# SR-Daughter.net
KiCad netlist of a schematic drawn in EAGLE
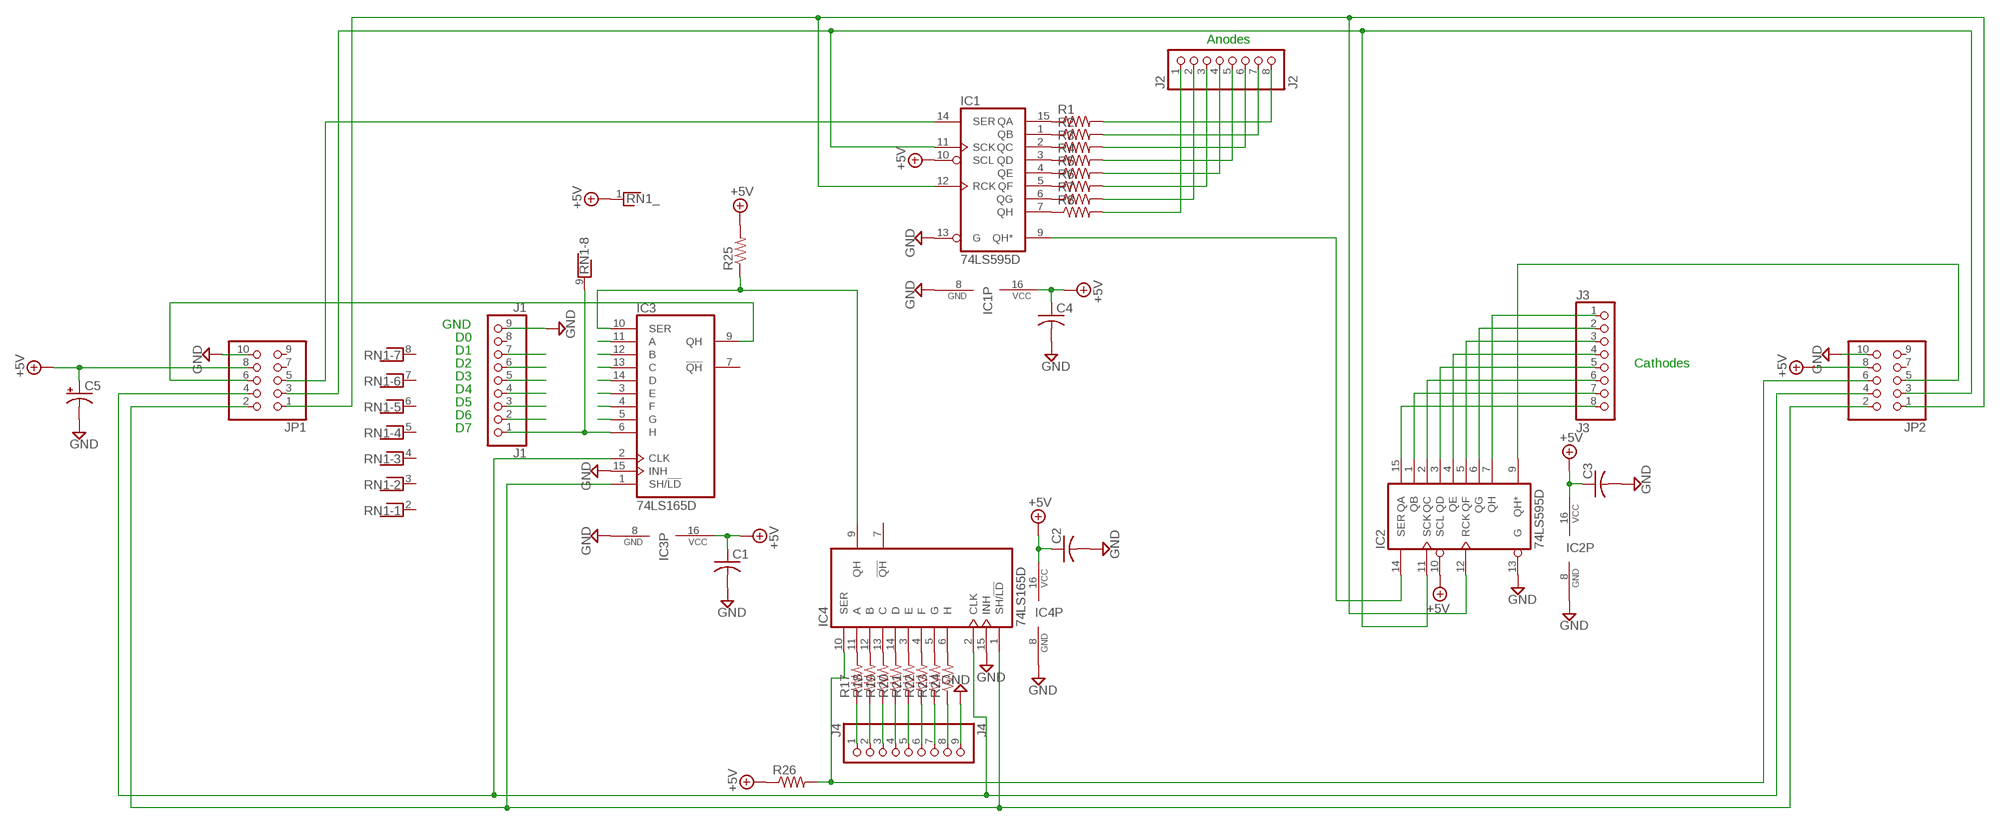
[diagram p0: schematic, sheet 1]

(export (version "E")
  (design (tool "Eeschema 10.0.6"))
  (components
    (comp (ref "C1")
      (value "C-USC0603")
      (footprint "eagle-import:C0603")
      (libsource (lib "eagle-import") (part "C-USC0603"))
    )
    (comp (ref "C2")
      (value "C-USC0603")
      (footprint "eagle-import:C0603")
      (libsource (lib "eagle-import") (part "C-USC0603"))
    )
    (comp (ref "C3")
      (value "C-USC0603")
      (footprint "eagle-import:C0603")
      (libsource (lib "eagle-import") (part "C-USC0603"))
    )
    (comp (ref "C4")
      (value "C-USC0603")
      (footprint "eagle-import:C0603")
      (libsource (lib "eagle-import") (part "C-USC0603"))
    )
    (comp (ref "C5")
      (value "CPOL-USE2-5")
      (footprint "eagle-import:E2-5")
      (libsource (lib "eagle-import") (part "CPOL-USE2-5"))
    )
    (comp (ref "IC1")
      (value "74LS595D")
      (footprint "eagle-import:SO16")
      (libsource (lib "eagle-import") (part "74595DLS"))
    )
    (comp (ref "IC2")
      (value "74LS595D")
      (footprint "eagle-import:SO16")
      (libsource (lib "eagle-import") (part "74595DLS"))
    )
    (comp (ref "IC3")
      (value "74LS165D")
      (footprint "eagle-import:SO16")
      (libsource (lib "eagle-import") (part "74165DLS"))
    )
    (comp (ref "IC4")
      (value "74LS165D")
      (footprint "eagle-import:SO16")
      (libsource (lib "eagle-import") (part "74165DLS"))
    )
    (comp (ref "J1")
      (value "J1")
      (footprint "eagle-import:1X09")
      (libsource (lib "eagle-import") (part "PINHD-1X9"))
    )
    (comp (ref "J2")
      (value "J2")
      (footprint "eagle-import:1X08")
      (libsource (lib "eagle-import") (part "PINHD-1X8"))
    )
    (comp (ref "J3")
      (value "J3")
      (footprint "eagle-import:1X08")
      (libsource (lib "eagle-import") (part "PINHD-1X8"))
    )
    (comp (ref "J4")
      (value "J4")
      (footprint "eagle-import:1X09")
      (libsource (lib "eagle-import") (part "PINHD-1X9"))
    )
    (comp (ref "JP1")
      (value "PINHD-2X5")
      (footprint "eagle-import:2X05")
      (libsource (lib "eagle-import") (part "PINHD-2X5"))
    )
    (comp (ref "JP2")
      (value "PINHD-2X5")
      (footprint "eagle-import:2X05")
      (libsource (lib "eagle-import") (part "PINHD-2X5"))
    )
    (comp (ref "R1")
      (value "R-US_M0805")
      (footprint "eagle-import:M0805")
      (libsource (lib "eagle-import") (part "R-US_M0805"))
    )
    (comp (ref "R2")
      (value "R-US_M0805")
      (footprint "eagle-import:M0805")
      (libsource (lib "eagle-import") (part "R-US_M0805"))
    )
    (comp (ref "R3")
      (value "R-US_M0805")
      (footprint "eagle-import:M0805")
      (libsource (lib "eagle-import") (part "R-US_M0805"))
    )
    (comp (ref "R4")
      (value "R-US_M0805")
      (footprint "eagle-import:M0805")
      (libsource (lib "eagle-import") (part "R-US_M0805"))
    )
    (comp (ref "R5")
      (value "R-US_M0805")
      (footprint "eagle-import:M0805")
      (libsource (lib "eagle-import") (part "R-US_M0805"))
    )
    (comp (ref "R6")
      (value "R-US_M0805")
      (footprint "eagle-import:M0805")
      (libsource (lib "eagle-import") (part "R-US_M0805"))
    )
    (comp (ref "R7")
      (value "R-US_M0805")
      (footprint "eagle-import:M0805")
      (libsource (lib "eagle-import") (part "R-US_M0805"))
    )
    (comp (ref "R8")
      (value "R-US_M0805")
      (footprint "eagle-import:M0805")
      (libsource (lib "eagle-import") (part "R-US_M0805"))
    )
    (comp (ref "R17")
      (value "R-US_M0805")
      (footprint "eagle-import:M0805")
      (libsource (lib "eagle-import") (part "R-US_M0805"))
    )
    (comp (ref "R18")
      (value "R-US_M0805")
      (footprint "eagle-import:M0805")
      (libsource (lib "eagle-import") (part "R-US_M0805"))
    )
    (comp (ref "R19")
      (value "R-US_M0805")
      (footprint "eagle-import:M0805")
      (libsource (lib "eagle-import") (part "R-US_M0805"))
    )
    (comp (ref "R20")
      (value "R-US_M0805")
      (footprint "eagle-import:M0805")
      (libsource (lib "eagle-import") (part "R-US_M0805"))
    )
    (comp (ref "R21")
      (value "R-US_M0805")
      (footprint "eagle-import:M0805")
      (libsource (lib "eagle-import") (part "R-US_M0805"))
    )
    (comp (ref "R22")
      (value "R-US_M0805")
      (footprint "eagle-import:M0805")
      (libsource (lib "eagle-import") (part "R-US_M0805"))
    )
    (comp (ref "R23")
      (value "R-US_M0805")
      (footprint "eagle-import:M0805")
      (libsource (lib "eagle-import") (part "R-US_M0805"))
    )
    (comp (ref "R24")
      (value "R-US_M0805")
      (footprint "eagle-import:M0805")
      (libsource (lib "eagle-import") (part "R-US_M0805"))
    )
    (comp (ref "R25")
      (value "R-US_M0805")
      (footprint "eagle-import:M0805")
      (libsource (lib "eagle-import") (part "R-US_M0805"))
    )
    (comp (ref "R26")
      (value "R-US_M0805")
      (footprint "eagle-import:M0805")
      (libsource (lib "eagle-import") (part "R-US_M0805"))
    )
    (comp (ref "RN1")
      (value "RNX8")
      (footprint "eagle-import:RN-9")
      (libsource (lib "eagle-import") (part "RNX8"))
    )
  )
  (nets
    (net (code "1") (name "+5V") (class "Default")
      (node (ref "C1") (pin "1") (pinfunction "1_1") (pintype "passive"))
      (node (ref "C2") (pin "1") (pinfunction "1_1") (pintype "passive"))
      (node (ref "C3") (pin "1") (pinfunction "1_1") (pintype "passive"))
      (node (ref "C4") (pin "1") (pinfunction "1_1") (pintype "passive"))
      (node (ref "C5") (pin "+") (pinfunction "+_+") (pintype "passive"))
      (node (ref "IC1") (pin "10") (pinfunction "SCL_10") (pintype "input"))
      (node (ref "IC1") (pin "16") (pinfunction "VCC_16") (pintype "power_in"))
      (node (ref "IC2") (pin "10") (pinfunction "SCL_10") (pintype "input"))
      (node (ref "IC2") (pin "16") (pinfunction "VCC_16") (pintype "power_in"))
      (node (ref "IC3") (pin "16") (pinfunction "VCC_16") (pintype "power_in"))
      (node (ref "IC4") (pin "16") (pinfunction "VCC_16") (pintype "power_in"))
      (node (ref "JP1") (pin "8") (pinfunction "8_8") (pintype "passive"))
      (node (ref "JP2") (pin "8") (pinfunction "8_8") (pintype "passive"))
      (node (ref "R25") (pin "2") (pinfunction "2_2") (pintype "passive"))
      (node (ref "R26") (pin "1") (pinfunction "1_1") (pintype "passive"))
      (node (ref "RN1") (pin "1") (pinfunction "1_1") (pintype "passive"))
    )
    (net (code "2") (name "GND") (class "Default")
      (node (ref "C1") (pin "2") (pinfunction "2_2") (pintype "passive"))
      (node (ref "C2") (pin "2") (pinfunction "2_2") (pintype "passive"))
      (node (ref "C3") (pin "2") (pinfunction "2_2") (pintype "passive"))
      (node (ref "C4") (pin "2") (pinfunction "2_2") (pintype "passive"))
      (node (ref "C5") (pin "-") (pinfunction "-_-") (pintype "passive"))
      (node (ref "IC1") (pin "13") (pinfunction "G_13") (pintype "input"))
      (node (ref "IC1") (pin "8") (pinfunction "GND_8") (pintype "power_in"))
      (node (ref "IC2") (pin "13") (pinfunction "G_13") (pintype "input"))
      (node (ref "IC2") (pin "8") (pinfunction "GND_8") (pintype "power_in"))
      (node (ref "IC3") (pin "15") (pinfunction "INH_15") (pintype "input"))
      (node (ref "IC3") (pin "8") (pinfunction "GND_8") (pintype "power_in"))
      (node (ref "IC4") (pin "15") (pinfunction "INH_15") (pintype "input"))
      (node (ref "IC4") (pin "8") (pinfunction "GND_8") (pintype "power_in"))
      (node (ref "J1") (pin "9") (pinfunction "9_9") (pintype "passive"))
      (node (ref "J4") (pin "9") (pinfunction "9_9") (pintype "passive"))
      (node (ref "JP1") (pin "10") (pinfunction "10_10") (pintype "passive"))
      (node (ref "JP2") (pin "10") (pinfunction "10_10") (pintype "passive"))
    )
    (net (code "3") (name "Net-(IC1A-QA)") (class "Default")
      (node (ref "IC1") (pin "15") (pinfunction "QA_15") (pintype "tri_state"))
      (node (ref "R1") (pin "1") (pinfunction "1_1") (pintype "passive"))
    )
    (net (code "4") (name "Net-(IC1A-QB)") (class "Default")
      (node (ref "IC1") (pin "1") (pinfunction "QB_1") (pintype "tri_state"))
      (node (ref "R2") (pin "1") (pinfunction "1_1") (pintype "passive"))
    )
    (net (code "5") (name "Net-(IC1A-QC)") (class "Default")
      (node (ref "IC1") (pin "2") (pinfunction "QC_2") (pintype "tri_state"))
      (node (ref "R3") (pin "1") (pinfunction "1_1") (pintype "passive"))
    )
    (net (code "6") (name "Net-(IC1A-QD)") (class "Default")
      (node (ref "IC1") (pin "3") (pinfunction "QD_3") (pintype "tri_state"))
      (node (ref "R4") (pin "1") (pinfunction "1_1") (pintype "passive"))
    )
    (net (code "7") (name "Net-(IC1A-QE)") (class "Default")
      (node (ref "IC1") (pin "4") (pinfunction "QE_4") (pintype "tri_state"))
      (node (ref "R5") (pin "1") (pinfunction "1_1") (pintype "passive"))
    )
    (net (code "8") (name "Net-(IC1A-QF)") (class "Default")
      (node (ref "IC1") (pin "5") (pinfunction "QF_5") (pintype "tri_state"))
      (node (ref "R6") (pin "1") (pinfunction "1_1") (pintype "passive"))
    )
    (net (code "9") (name "Net-(IC1A-QG)") (class "Default")
      (node (ref "IC1") (pin "6") (pinfunction "QG_6") (pintype "tri_state"))
      (node (ref "R7") (pin "1") (pinfunction "1_1") (pintype "passive"))
    )
    (net (code "10") (name "Net-(IC1A-QH)") (class "Default")
      (node (ref "IC1") (pin "7") (pinfunction "QH_7") (pintype "tri_state"))
      (node (ref "R8") (pin "1") (pinfunction "1_1") (pintype "passive"))
    )
    (net (code "11") (name "Net-(IC1A-QH*)") (class "Default")
      (node (ref "IC1") (pin "9") (pinfunction "QH*_9") (pintype "tri_state"))
      (node (ref "IC2") (pin "14") (pinfunction "SER_14") (pintype "input"))
    )
    (net (code "12") (name "Net-(IC1A-RCK)") (class "Default")
      (node (ref "IC1") (pin "12") (pinfunction "RCK_12") (pintype "input"))
      (node (ref "IC2") (pin "12") (pinfunction "RCK_12") (pintype "input"))
      (node (ref "JP1") (pin "1") (pinfunction "1_1") (pintype "passive"))
      (node (ref "JP2") (pin "1") (pinfunction "1_1") (pintype "passive"))
    )
    (net (code "13") (name "Net-(IC1A-SCK)") (class "Default")
      (node (ref "IC1") (pin "11") (pinfunction "SCK_11") (pintype "input"))
      (node (ref "IC2") (pin "11") (pinfunction "SCK_11") (pintype "input"))
      (node (ref "JP1") (pin "3") (pinfunction "3_3") (pintype "passive"))
      (node (ref "JP2") (pin "3") (pinfunction "3_3") (pintype "passive"))
    )
    (net (code "14") (name "Net-(IC1A-SER)") (class "Default")
      (node (ref "IC1") (pin "14") (pinfunction "SER_14") (pintype "input"))
      (node (ref "JP1") (pin "5") (pinfunction "5_5") (pintype "passive"))
    )
    (net (code "15") (name "Net-(IC2A-QA)") (class "Default")
      (node (ref "IC2") (pin "15") (pinfunction "QA_15") (pintype "tri_state"))
      (node (ref "J3") (pin "8") (pinfunction "8_8") (pintype "passive"))
    )
    (net (code "16") (name "Net-(IC2A-QB)") (class "Default")
      (node (ref "IC2") (pin "1") (pinfunction "QB_1") (pintype "tri_state"))
      (node (ref "J3") (pin "7") (pinfunction "7_7") (pintype "passive"))
    )
    (net (code "17") (name "Net-(IC2A-QC)") (class "Default")
      (node (ref "IC2") (pin "2") (pinfunction "QC_2") (pintype "tri_state"))
      (node (ref "J3") (pin "6") (pinfunction "6_6") (pintype "passive"))
    )
    (net (code "18") (name "Net-(IC2A-QD)") (class "Default")
      (node (ref "IC2") (pin "3") (pinfunction "QD_3") (pintype "tri_state"))
      (node (ref "J3") (pin "5") (pinfunction "5_5") (pintype "passive"))
    )
    (net (code "19") (name "Net-(IC2A-QE)") (class "Default")
      (node (ref "IC2") (pin "4") (pinfunction "QE_4") (pintype "tri_state"))
      (node (ref "J3") (pin "4") (pinfunction "4_4") (pintype "passive"))
    )
    (net (code "20") (name "Net-(IC2A-QF)") (class "Default")
      (node (ref "IC2") (pin "5") (pinfunction "QF_5") (pintype "tri_state"))
      (node (ref "J3") (pin "3") (pinfunction "3_3") (pintype "passive"))
    )
    (net (code "21") (name "Net-(IC2A-QG)") (class "Default")
      (node (ref "IC2") (pin "6") (pinfunction "QG_6") (pintype "tri_state"))
      (node (ref "J3") (pin "2") (pinfunction "2_2") (pintype "passive"))
    )
    (net (code "22") (name "Net-(IC2A-QH)") (class "Default")
      (node (ref "IC2") (pin "7") (pinfunction "QH_7") (pintype "tri_state"))
      (node (ref "J3") (pin "1") (pinfunction "1_1") (pintype "passive"))
    )
    (net (code "23") (name "Net-(IC2A-QH*)") (class "Default")
      (node (ref "IC2") (pin "9") (pinfunction "QH*_9") (pintype "tri_state"))
      (node (ref "JP2") (pin "5") (pinfunction "5_5") (pintype "passive"))
    )
    (net (code "24") (name "Net-(IC3A-CLK)") (class "Default")
      (node (ref "IC3") (pin "2") (pinfunction "CLK_2") (pintype "input"))
      (node (ref "IC4") (pin "2") (pinfunction "CLK_2") (pintype "input"))
      (node (ref "JP1") (pin "4") (pinfunction "4_4") (pintype "passive"))
      (node (ref "JP2") (pin "4") (pinfunction "4_4") (pintype "passive"))
    )
    (net (code "25") (name "Net-(IC3A-H)") (class "Default")
      (node (ref "IC3") (pin "6") (pinfunction "H_6") (pintype "input"))
      (node (ref "J1") (pin "1") (pinfunction "1_1") (pintype "passive"))
      (node (ref "RN1") (pin "9") (pinfunction "1_9") (pintype "passive"))
    )
    (net (code "26") (name "Net-(IC3A-QH)") (class "Default")
      (node (ref "IC3") (pin "9") (pinfunction "QH_9") (pintype "output"))
      (node (ref "JP1") (pin "6") (pinfunction "6_6") (pintype "passive"))
    )
    (net (code "27") (name "Net-(IC3A-SER)") (class "Default")
      (node (ref "IC3") (pin "10") (pinfunction "SER_10") (pintype "input"))
      (node (ref "IC4") (pin "9") (pinfunction "QH_9") (pintype "output"))
      (node (ref "R25") (pin "1") (pinfunction "1_1") (pintype "passive"))
    )
    (net (code "28") (name "Net-(IC3A-SH{slash}~{LD})") (class "Default")
      (node (ref "IC3") (pin "1") (pinfunction "SH/~{LD}_1") (pintype "input"))
      (node (ref "IC4") (pin "1") (pinfunction "SH/~{LD}_1") (pintype "input"))
      (node (ref "JP1") (pin "2") (pinfunction "2_2") (pintype "passive"))
      (node (ref "JP2") (pin "2") (pinfunction "2_2") (pintype "passive"))
    )
    (net (code "29") (name "Net-(IC4A-A)") (class "Default")
      (node (ref "IC4") (pin "11") (pinfunction "A_11") (pintype "input"))
      (node (ref "R17") (pin "2") (pinfunction "2_2") (pintype "passive"))
    )
    (net (code "30") (name "Net-(IC4A-B)") (class "Default")
      (node (ref "IC4") (pin "12") (pinfunction "B_12") (pintype "input"))
      (node (ref "R18") (pin "2") (pinfunction "2_2") (pintype "passive"))
    )
    (net (code "31") (name "Net-(IC4A-C)") (class "Default")
      (node (ref "IC4") (pin "13") (pinfunction "C_13") (pintype "input"))
      (node (ref "R19") (pin "2") (pinfunction "2_2") (pintype "passive"))
    )
    (net (code "32") (name "Net-(IC4A-D)") (class "Default")
      (node (ref "IC4") (pin "14") (pinfunction "D_14") (pintype "input"))
      (node (ref "R20") (pin "2") (pinfunction "2_2") (pintype "passive"))
    )
    (net (code "33") (name "Net-(IC4A-E)") (class "Default")
      (node (ref "IC4") (pin "3") (pinfunction "E_3") (pintype "input"))
      (node (ref "R21") (pin "2") (pinfunction "2_2") (pintype "passive"))
    )
    (net (code "34") (name "Net-(IC4A-F)") (class "Default")
      (node (ref "IC4") (pin "4") (pinfunction "F_4") (pintype "input"))
      (node (ref "R22") (pin "2") (pinfunction "2_2") (pintype "passive"))
    )
    (net (code "35") (name "Net-(IC4A-G)") (class "Default")
      (node (ref "IC4") (pin "5") (pinfunction "G_5") (pintype "input"))
      (node (ref "R23") (pin "2") (pinfunction "2_2") (pintype "passive"))
    )
    (net (code "36") (name "Net-(IC4A-H)") (class "Default")
      (node (ref "IC4") (pin "6") (pinfunction "H_6") (pintype "input"))
      (node (ref "R24") (pin "2") (pinfunction "2_2") (pintype "passive"))
    )
    (net (code "37") (name "Net-(IC4A-SER)") (class "Default")
      (node (ref "IC4") (pin "10") (pinfunction "SER_10") (pintype "input"))
      (node (ref "JP2") (pin "6") (pinfunction "6_6") (pintype "passive"))
      (node (ref "R26") (pin "2") (pinfunction "2_2") (pintype "passive"))
    )
    (net (code "38") (name "Net-(J2-Pad1)") (class "Default")
      (node (ref "J2") (pin "1") (pinfunction "1_1") (pintype "passive"))
      (node (ref "R8") (pin "2") (pinfunction "2_2") (pintype "passive"))
    )
    (net (code "39") (name "Net-(J2-Pad2)") (class "Default")
      (node (ref "J2") (pin "2") (pinfunction "2_2") (pintype "passive"))
      (node (ref "R7") (pin "2") (pinfunction "2_2") (pintype "passive"))
    )
    (net (code "40") (name "Net-(J2-Pad3)") (class "Default")
      (node (ref "J2") (pin "3") (pinfunction "3_3") (pintype "passive"))
      (node (ref "R6") (pin "2") (pinfunction "2_2") (pintype "passive"))
    )
    (net (code "41") (name "Net-(J2-Pad4)") (class "Default")
      (node (ref "J2") (pin "4") (pinfunction "4_4") (pintype "passive"))
      (node (ref "R5") (pin "2") (pinfunction "2_2") (pintype "passive"))
    )
    (net (code "42") (name "Net-(J2-Pad5)") (class "Default")
      (node (ref "J2") (pin "5") (pinfunction "5_5") (pintype "passive"))
      (node (ref "R4") (pin "2") (pinfunction "2_2") (pintype "passive"))
    )
    (net (code "43") (name "Net-(J2-Pad6)") (class "Default")
      (node (ref "J2") (pin "6") (pinfunction "6_6") (pintype "passive"))
      (node (ref "R3") (pin "2") (pinfunction "2_2") (pintype "passive"))
    )
    (net (code "44") (name "Net-(J2-Pad7)") (class "Default")
      (node (ref "J2") (pin "7") (pinfunction "7_7") (pintype "passive"))
      (node (ref "R2") (pin "2") (pinfunction "2_2") (pintype "passive"))
    )
    (net (code "45") (name "Net-(J2-Pad8)") (class "Default")
      (node (ref "J2") (pin "8") (pinfunction "8_8") (pintype "passive"))
      (node (ref "R1") (pin "2") (pinfunction "2_2") (pintype "passive"))
    )
    (net (code "46") (name "Net-(J4-Pad1)") (class "Default")
      (node (ref "J4") (pin "1") (pinfunction "1_1") (pintype "passive"))
      (node (ref "R17") (pin "1") (pinfunction "1_1") (pintype "passive"))
    )
    (net (code "47") (name "Net-(J4-Pad2)") (class "Default")
      (node (ref "J4") (pin "2") (pinfunction "2_2") (pintype "passive"))
      (node (ref "R18") (pin "1") (pinfunction "1_1") (pintype "passive"))
    )
    (net (code "48") (name "Net-(J4-Pad3)") (class "Default")
      (node (ref "J4") (pin "3") (pinfunction "3_3") (pintype "passive"))
      (node (ref "R19") (pin "1") (pinfunction "1_1") (pintype "passive"))
    )
    (net (code "49") (name "Net-(J4-Pad4)") (class "Default")
      (node (ref "J4") (pin "4") (pinfunction "4_4") (pintype "passive"))
      (node (ref "R20") (pin "1") (pinfunction "1_1") (pintype "passive"))
    )
    (net (code "50") (name "Net-(J4-Pad5)") (class "Default")
      (node (ref "J4") (pin "5") (pinfunction "5_5") (pintype "passive"))
      (node (ref "R21") (pin "1") (pinfunction "1_1") (pintype "passive"))
    )
    (net (code "51") (name "Net-(J4-Pad6)") (class "Default")
      (node (ref "J4") (pin "6") (pinfunction "6_6") (pintype "passive"))
      (node (ref "R22") (pin "1") (pinfunction "1_1") (pintype "passive"))
    )
    (net (code "52") (name "Net-(J4-Pad7)") (class "Default")
      (node (ref "J4") (pin "7") (pinfunction "7_7") (pintype "passive"))
      (node (ref "R23") (pin "1") (pinfunction "1_1") (pintype "passive"))
    )
    (net (code "53") (name "Net-(J4-Pad8)") (class "Default")
      (node (ref "J4") (pin "8") (pinfunction "8_8") (pintype "passive"))
      (node (ref "R24") (pin "1") (pinfunction "1_1") (pintype "passive"))
    )
    (net (code "54") (name "unconnected-(IC3A-A-Pad11)") (class "Default")
      (node (ref "IC3") (pin "11") (pinfunction "A_11") (pintype "input"))
    )
    (net (code "55") (name "unconnected-(IC3A-B-Pad12)") (class "Default")
      (node (ref "IC3") (pin "12") (pinfunction "B_12") (pintype "input"))
    )
    (net (code "56") (name "unconnected-(IC3A-C-Pad13)") (class "Default")
      (node (ref "IC3") (pin "13") (pinfunction "C_13") (pintype "input"))
    )
    (net (code "57") (name "unconnected-(IC3A-D-Pad14)") (class "Default")
      (node (ref "IC3") (pin "14") (pinfunction "D_14") (pintype "input"))
    )
    (net (code "58") (name "unconnected-(IC3A-E-Pad3)") (class "Default")
      (node (ref "IC3") (pin "3") (pinfunction "E_3") (pintype "input"))
    )
    (net (code "59") (name "unconnected-(IC3A-F-Pad4)") (class "Default")
      (node (ref "IC3") (pin "4") (pinfunction "F_4") (pintype "input"))
    )
    (net (code "60") (name "unconnected-(IC3A-G-Pad5)") (class "Default")
      (node (ref "IC3") (pin "5") (pinfunction "G_5") (pintype "input"))
    )
    (net (code "61") (name "unconnected-(IC3A-~{QH}-Pad7)") (class "Default")
      (node (ref "IC3") (pin "7") (pinfunction "~{QH}_7") (pintype "output"))
    )
    (net (code "62") (name "unconnected-(IC4A-~{QH}-Pad7)") (class "Default")
      (node (ref "IC4") (pin "7") (pinfunction "~{QH}_7") (pintype "output"))
    )
    (net (code "63") (name "unconnected-(J1-Pad2)") (class "Default")
      (node (ref "J1") (pin "2") (pinfunction "2_2") (pintype "passive"))
    )
    (net (code "64") (name "unconnected-(J1-Pad3)") (class "Default")
      (node (ref "J1") (pin "3") (pinfunction "3_3") (pintype "passive"))
    )
    (net (code "65") (name "unconnected-(J1-Pad4)") (class "Default")
      (node (ref "J1") (pin "4") (pinfunction "4_4") (pintype "passive"))
    )
    (net (code "66") (name "unconnected-(J1-Pad5)") (class "Default")
      (node (ref "J1") (pin "5") (pinfunction "5_5") (pintype "passive"))
    )
    (net (code "67") (name "unconnected-(J1-Pad6)") (class "Default")
      (node (ref "J1") (pin "6") (pinfunction "6_6") (pintype "passive"))
    )
    (net (code "68") (name "unconnected-(J1-Pad7)") (class "Default")
      (node (ref "J1") (pin "7") (pinfunction "7_7") (pintype "passive"))
    )
    (net (code "69") (name "unconnected-(J1-Pad8)") (class "Default")
      (node (ref "J1") (pin "8") (pinfunction "8_8") (pintype "passive"))
    )
    (net (code "70") (name "unconnected-(JP1-Pad7)") (class "Default")
      (node (ref "JP1") (pin "7") (pinfunction "7_7") (pintype "passive"))
    )
    (net (code "71") (name "unconnected-(JP1-Pad9)") (class "Default")
      (node (ref "JP1") (pin "9") (pinfunction "9_9") (pintype "passive"))
    )
    (net (code "72") (name "unconnected-(JP2-Pad7)") (class "Default")
      (node (ref "JP2") (pin "7") (pinfunction "7_7") (pintype "passive"))
    )
    (net (code "73") (name "unconnected-(JP2-Pad9)") (class "Default")
      (node (ref "JP2") (pin "9") (pinfunction "9_9") (pintype "passive"))
    )
    (net (code "74") (name "unconnected-(RN1A-1-Pad2)") (class "Default")
      (node (ref "RN1") (pin "2") (pinfunction "1_2") (pintype "passive"))
    )
    (net (code "75") (name "unconnected-(RN1B-1-Pad3)") (class "Default")
      (node (ref "RN1") (pin "3") (pinfunction "1_3") (pintype "passive"))
    )
    (net (code "76") (name "unconnected-(RN1C-1-Pad4)") (class "Default")
      (node (ref "RN1") (pin "4") (pinfunction "1_4") (pintype "passive"))
    )
    (net (code "77") (name "unconnected-(RN1D-1-Pad5)") (class "Default")
      (node (ref "RN1") (pin "5") (pinfunction "1_5") (pintype "passive"))
    )
    (net (code "78") (name "unconnected-(RN1E-1-Pad6)") (class "Default")
      (node (ref "RN1") (pin "6") (pinfunction "1_6") (pintype "passive"))
    )
    (net (code "79") (name "unconnected-(RN1F-1-Pad7)") (class "Default")
      (node (ref "RN1") (pin "7") (pinfunction "1_7") (pintype "passive"))
    )
    (net (code "80") (name "unconnected-(RN1G-1-Pad8)") (class "Default")
      (node (ref "RN1") (pin "8") (pinfunction "1_8") (pintype "passive"))
    )
  )
)
